# controlled_boost_converter_ch0.net
KiCad netlist of a schematic drawn in Altium Designer
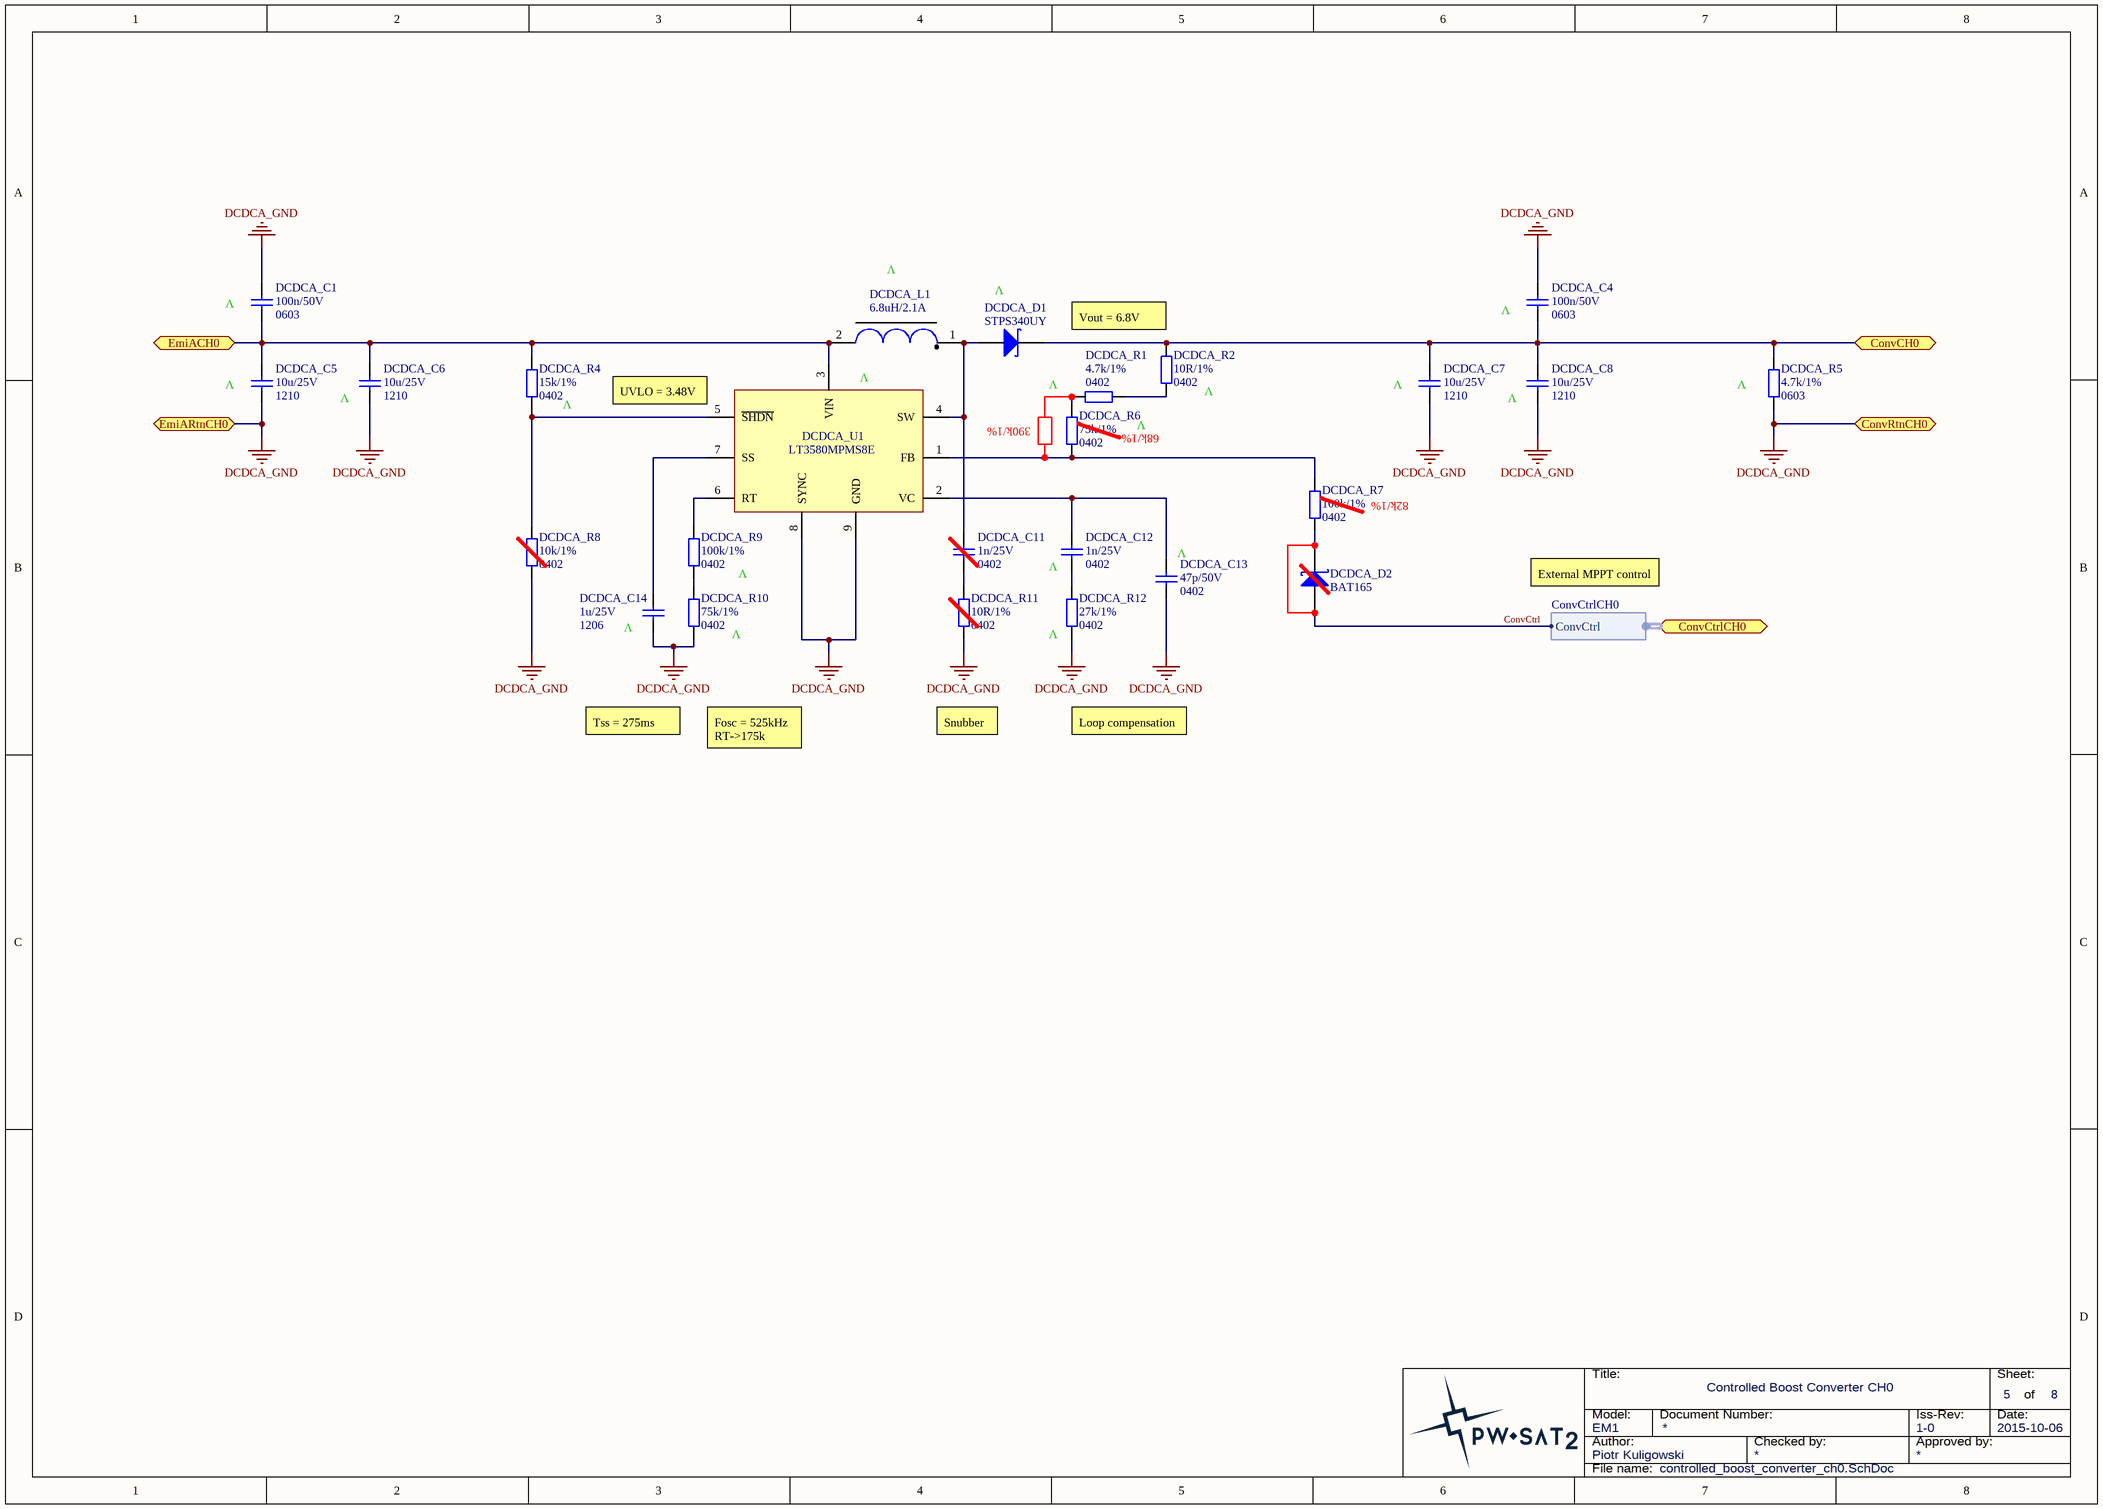
[diagram p0: controlled_boost_converter_ch0.SchDoc]

(export (version "E")
  (design (tool "Eeschema 10.0.6"))
  (components
    (comp (ref "DCDCA_C1")
      (value "100n/50V")
      (footprint "SMD_Capacitor_0603")
      (description "Ceramic Cap Kemet COTS 100n/50V X7R 0603")
      (fields
        (field (name "MANUFACTURER") "Kemet")
        (field (name "MANUFACTURERPARTNUMBER") "C0603T104K5RALTU")
        (field (name "PACKAGE") "0603")
      )
      (libsource (lib "capacitors") (part "Cer_C0603T104K5RALTU"))
    )
    (comp (ref "DCDCA_C4")
      (value "100n/50V")
      (footprint "SMD_Capacitor_0603")
      (description "Ceramic Cap Kemet COTS 100n/50V X7R 0603")
      (fields
        (field (name "MANUFACTURER") "Kemet")
        (field (name "MANUFACTURERPARTNUMBER") "C0603T104K5RALTU")
        (field (name "PACKAGE") "0603")
      )
      (libsource (lib "capacitors") (part "Cer_C0603T104K5RALTU"))
    )
    (comp (ref "DCDCA_C5")
      (value "10u/25V")
      (footprint "SMD_Capacitor_1210")
      (description "Ceramic Cap Murata Automotive 10u/25V X7R 1210")
      (fields
        (field (name "MANUFACTURER") "Murata")
        (field (name "MANUFACTURERPARTNUMBER") "GCJ32ER71E106KA12L")
        (field (name "PACKAGE") "1210")
      )
      (libsource (lib "capacitors") (part "Cer_GCJ32ER71E106KA12L"))
    )
    (comp (ref "DCDCA_C6")
      (value "10u/25V")
      (footprint "SMD_Capacitor_1210")
      (description "Ceramic Cap Murata Automotive 10u/25V X7R 1210")
      (fields
        (field (name "MANUFACTURER") "Murata")
        (field (name "MANUFACTURERPARTNUMBER") "GCJ32ER71E106KA12L")
        (field (name "PACKAGE") "1210")
      )
      (libsource (lib "capacitors") (part "Cer_GCJ32ER71E106KA12L"))
    )
    (comp (ref "DCDCA_C7")
      (value "10u/25V")
      (footprint "SMD_Capacitor_1210")
      (description "Ceramic Cap Murata Automotive 10u/25V X7R 1210")
      (fields
        (field (name "MANUFACTURER") "Murata")
        (field (name "MANUFACTURERPARTNUMBER") "GCJ32ER71E106KA12L")
        (field (name "PACKAGE") "1210")
      )
      (libsource (lib "capacitors") (part "Cer_GCJ32ER71E106KA12L"))
    )
    (comp (ref "DCDCA_C8")
      (value "10u/25V")
      (footprint "SMD_Capacitor_1210")
      (description "Ceramic Cap Murata Automotive 10u/25V X7R 1210")
      (fields
        (field (name "MANUFACTURER") "Murata")
        (field (name "MANUFACTURERPARTNUMBER") "GCJ32ER71E106KA12L")
        (field (name "PACKAGE") "1210")
      )
      (libsource (lib "capacitors") (part "Cer_GCJ32ER71E106KA12L"))
    )
    (comp (ref "DCDCA_C11")
      (value "1n/25V")
      (footprint "SMD_Capacitor_0402")
      (description "Ceramic Cap Kemet COTS 1n/25V C0G 0402.")
      (fields
        (field (name "MANUFACTURER") "Kemet")
        (field (name "MANUFACTURERPARTNUMBER") "C0402T102K3GAL")
        (field (name "PACKAGE") "0402")
      )
      (libsource (lib "capacitors") (part "Cer_C0402T102K3GAL"))
    )
    (comp (ref "DCDCA_C12")
      (value "1n/25V")
      (footprint "SMD_Capacitor_0402")
      (description "Ceramic Cap Kemet COTS 1n/25V C0G 0402.")
      (fields
        (field (name "MANUFACTURER") "Kemet")
        (field (name "MANUFACTURERPARTNUMBER") "C0402T102K3GAL")
        (field (name "PACKAGE") "0402")
      )
      (libsource (lib "capacitors") (part "Cer_C0402T102K3GAL"))
    )
    (comp (ref "DCDCA_C13")
      (value "47p/50V")
      (footprint "SMD_Capacitor_0402")
      (description "Ceramic Cap Murata Automotive 47p/50V C0G 0402")
      (fields
        (field (name "MANUFACTURER") "Murata")
        (field (name "MANUFACTURERPARTNUMBER") "GCM1555C1H470JA16D")
        (field (name "PACKAGE") "0402")
      )
      (libsource (lib "capacitors") (part "Cer_GCM1555C1H470JA16D"))
    )
    (comp (ref "DCDCA_C14")
      (value "1u/25V")
      (footprint "SMD_Capacitor_1206")
      (description "Ceramic Cap Kemet COTS 1u/25V X7R 1206")
      (fields
        (field (name "MANUFACTURERPARTNUMBER") "C1206T105K3RALTU")
        (field (name "MANUFACTURER") "Kemet")
        (field (name "PACKAGE") "1206")
      )
      (libsource (lib "capacitors") (part "Cer_C1206T105K3RALTU"))
    )
    (comp (ref "DCDCA_D1")
      (value "STPS340UY")
      (footprint "DO-214AA")
      (description "3A/40V Power Schottky Rectifier.")
      (fields (field (name "MANUFACTURER") "STMicroelectronics"))
      (libsource (lib "diodes") (part "STPS340x"))
    )
    (comp (ref "DCDCA_D2")
      (value "BAT165")
      (footprint "SOD323")
      (description "Madium Power AF Schottky 750mA 40V Diode")
      (fields (field (name "MANUFACTURER") "Infineon"))
      (libsource (lib "diodes") (part "BAT165"))
    )
    (comp (ref "DCDCA_L1")
      (value "6.8uH/2.1A")
      (footprint "Coilcraft_MSS6132")
      (description "Coilcraft MSS6132 Inductor, L=6.8uH, Irise20deg=2.1A, ESR=52mR, SRF=47MHz.")
      (fields
        (field (name "MANUFACTURER") "Coilcraft")
        (field (name "MANUFACTURERPARTNUMBER") "MSS6132-682MLx")
      )
      (libsource (lib "inductors") (part "MSS6132-682MLx"))
    )
    (comp (ref "DCDCA_R1")
      (value "4.7k/1%")
      (footprint "SMD_Resistor_0402")
      (description "4.7k/1% Vishay CRCW 0402 Resistor. 63mW, 100ppm, 50V.")
      (fields
        (field (name "MANUFACTURERPARTNUMBER") "CRCW04024K70FKxxxx")
        (field (name "MANUFACTURER") "Vishay")
        (field (name "PACKAGE") "0402")
      )
      (libsource (lib "resistors") (part "CRCW04024K70FKxxxx"))
    )
    (comp (ref "DCDCA_R2")
      (value "10R/1%")
      (footprint "SMD_Resistor_0402")
      (description "10R/1% Vishay CRCW 0402 Resistor. 63mW, 100ppm, 50V.")
      (fields
        (field (name "MANUFACTURER") "Vishay")
        (field (name "MANUFACTURERPARTNUMBER") "CRCW040210R0FKxxxx")
        (field (name "PACKAGE") "0402")
      )
      (libsource (lib "resistors") (part "CRCW040210R0FKxxxx"))
    )
    (comp (ref "DCDCA_R4")
      (value "15k/1%")
      (footprint "SMD_Resistor_0402")
      (description "15k/1% Vishay CRCW 0402 Resistor. 63mW, 100ppm, 50V.")
      (fields
        (field (name "MANUFACTURER") "Vishay")
        (field (name "MANUFACTURERPARTNUMBER") "CRCW040215K0FKxxxx")
        (field (name "PACKAGE") "0402")
      )
      (libsource (lib "resistors") (part "CRCW040215K0FKxxxx"))
    )
    (comp (ref "DCDCA_R5")
      (value "4.7k/1%")
      (footprint "SMD_Resistor_0603")
      (description "4.7k/1% Vishay CRCW 0603 Resistor. 100mW, 100ppm, 75V.")
      (fields
        (field (name "MANUFACTURER") "Vishay")
        (field (name "MANUFACTUERPARTNUMBER") "CRCW06034K70FKxxxx")
        (field (name "PACKAGE") "0603")
      )
      (libsource (lib "resistors") (part "CRCW06034K70FKxxxx"))
    )
    (comp (ref "DCDCA_R6")
      (value "75k/1%")
      (footprint "SMD_Resistor_0402")
      (description "75k/1% Vishay CRCW 0402 Resistor. 63mW, 100ppm, 50V.")
      (fields
        (field (name "MANUFACTURERPARTNUMBER") "CRCW040275K0FK")
        (field (name "MANUFACTURER") "Vishay")
        (field (name "PACKAGE") "0402")
      )
      (libsource (lib "resistors") (part "CRCW040275K0FKxxxx"))
    )
    (comp (ref "DCDCA_R7")
      (value "100k/1%")
      (footprint "SMD_Resistor_0402")
      (description "100k/1% Vishay CRCW 0402 Resistor. 63mW, 100ppm, 50V.")
      (fields
        (field (name "MANUFACTURER") "Vishay")
        (field (name "MANUFACTURERPARTNUMBER") "CRCW0402100KFKxxxx")
        (field (name "PACKAGE") "0402")
      )
      (libsource (lib "resistors") (part "CRCW0402100KFKxxxx"))
    )
    (comp (ref "DCDCA_R8")
      (value "10k/1%")
      (footprint "SMD_Resistor_0402")
      (description "10k/1% Vishay CRCW 0402 Resistor. 63mW, 100ppm, 50V.")
      (fields
        (field (name "MANUFACTURER") "Vishay")
        (field (name "MANUFACTURERPARTNUMBER") "CRCW040210K0FKxxxx")
        (field (name "PACKAGE") "0402")
      )
      (libsource (lib "resistors") (part "CRCW040210K0FKxxxx"))
    )
    (comp (ref "DCDCA_R9")
      (value "100k/1%")
      (footprint "SMD_Resistor_0402")
      (description "100k/1% Vishay CRCW 0402 Resistor. 63mW, 100ppm, 50V.")
      (fields
        (field (name "MANUFACTURER") "Vishay")
        (field (name "MANUFACTURERPARTNUMBER") "CRCW0402100KFKxxxx")
        (field (name "PACKAGE") "0402")
      )
      (libsource (lib "resistors") (part "CRCW0402100KFKxxxx"))
    )
    (comp (ref "DCDCA_R10")
      (value "75k/1%")
      (footprint "SMD_Resistor_0402")
      (description "75k/1% Vishay CRCW 0402 Resistor. 63mW, 100ppm, 50V.")
      (fields
        (field (name "MANUFACTURERPARTNUMBER") "CRCW040275K0FK")
        (field (name "MANUFACTURER") "Vishay")
        (field (name "PACKAGE") "0402")
      )
      (libsource (lib "resistors") (part "CRCW040275K0FKxxxx"))
    )
    (comp (ref "DCDCA_R11")
      (value "10R/1%")
      (footprint "SMD_Resistor_0402")
      (description "10R/1% Vishay CRCW 0402 Resistor. 63mW, 100ppm, 50V.")
      (fields
        (field (name "MANUFACTURER") "Vishay")
        (field (name "MANUFACTURERPARTNUMBER") "CRCW040210R0FKxxxx")
        (field (name "PACKAGE") "0402")
      )
      (libsource (lib "resistors") (part "CRCW040210R0FKxxxx"))
    )
    (comp (ref "DCDCA_R12")
      (value "27k/1%")
      (footprint "SMD_Resistor_0402")
      (description "27k/1% Vishay CRCW 0402 Resistor. 63mW, 100ppm, 50V.")
      (fields
        (field (name "MANUFACTURER") "Vishay")
        (field (name "MANUFACTURERPARTNUMBER") "CRCW040227K0FKxxxx")
        (field (name "PACKAGE") "0402")
      )
      (libsource (lib "resistors") (part "CRCW040227K0FKxxxx"))
    )
    (comp (ref "DCDCA_U1")
      (value "~")
      (footprint "LT-MS8E-8-1880X1680TP_N")
      (description "Boost Conv 2A, Soft-Start, Synchro")
      (fields
        (field (name "MANUFACTURER") "Linear Technology")
        (field (name "MANUFACTURERPARTNUMBER") "LT3580MPMS8E")
      )
      (libsource (lib "microcircuits") (part "LT3580MPMS8E"))
    )
  )
  (nets
    (net (code "2") (name "/ConvCH0") (class "Default")
      (node (ref "DCDCA_C4") (pin "1") (pinfunction "1_1") (pintype "passive"))
      (node (ref "DCDCA_C7") (pin "1") (pinfunction "1_1") (pintype "passive"))
      (node (ref "DCDCA_C8") (pin "1") (pinfunction "1_1") (pintype "passive"))
      (node (ref "DCDCA_D1") (pin "K") (pinfunction "K_K") (pintype "passive"))
      (node (ref "DCDCA_R2") (pin "1") (pinfunction "1_1") (pintype "passive"))
      (node (ref "DCDCA_R5") (pin "1") (pinfunction "1_1") (pintype "passive"))
    )
    (net (code "3") (name "/ConvCtrl") (class "Default")
      (node (ref "DCDCA_D2") (pin "A") (pinfunction "A_A") (pintype "passive"))
    )
    (net (code "4") (name "/EmiACH0") (class "Default")
      (node (ref "DCDCA_C1") (pin "1") (pinfunction "1_1") (pintype "passive"))
      (node (ref "DCDCA_C5") (pin "1") (pinfunction "1_1") (pintype "passive"))
      (node (ref "DCDCA_C6") (pin "1") (pinfunction "1_1") (pintype "passive"))
      (node (ref "DCDCA_L1") (pin "2") (pinfunction "2_2") (pintype "passive"))
      (node (ref "DCDCA_R4") (pin "1") (pinfunction "1_1") (pintype "passive"))
      (node (ref "DCDCA_U1") (pin "3") (pinfunction "VIN_3") (pintype "power_in"))
    )
    (net (code "6") (name "DCDCA_GND") (class "Default")
      (node (ref "DCDCA_C1") (pin "2") (pinfunction "2_2") (pintype "passive"))
      (node (ref "DCDCA_C13") (pin "2") (pinfunction "2_2") (pintype "passive"))
      (node (ref "DCDCA_C14") (pin "2") (pinfunction "2_2") (pintype "passive"))
      (node (ref "DCDCA_C4") (pin "2") (pinfunction "2_2") (pintype "passive"))
      (node (ref "DCDCA_C5") (pin "2") (pinfunction "2_2") (pintype "passive"))
      (node (ref "DCDCA_C6") (pin "2") (pinfunction "2_2") (pintype "passive"))
      (node (ref "DCDCA_C7") (pin "2") (pinfunction "2_2") (pintype "passive"))
      (node (ref "DCDCA_C8") (pin "2") (pinfunction "2_2") (pintype "passive"))
      (node (ref "DCDCA_R10") (pin "2") (pinfunction "2_2") (pintype "passive"))
      (node (ref "DCDCA_R11") (pin "2") (pinfunction "2_2") (pintype "passive"))
      (node (ref "DCDCA_R12") (pin "2") (pinfunction "2_2") (pintype "passive"))
      (node (ref "DCDCA_R5") (pin "2") (pinfunction "2_2") (pintype "passive"))
      (node (ref "DCDCA_R8") (pin "2") (pinfunction "2_2") (pintype "passive"))
      (node (ref "DCDCA_U1") (pin "8") (pinfunction "SYNC_8") (pintype "passive"))
      (node (ref "DCDCA_U1") (pin "9") (pinfunction "GND_9") (pintype "passive"))
    )
    (net (code "7") (name "Net-(DCDCA_C11-Pad2)") (class "Default")
      (node (ref "DCDCA_C11") (pin "2") (pinfunction "2_2") (pintype "passive"))
      (node (ref "DCDCA_R11") (pin "1") (pinfunction "1_1") (pintype "passive"))
    )
    (net (code "8") (name "Net-(DCDCA_C12-Pad2)") (class "Default")
      (node (ref "DCDCA_C12") (pin "2") (pinfunction "2_2") (pintype "passive"))
      (node (ref "DCDCA_R12") (pin "1") (pinfunction "1_1") (pintype "passive"))
    )
    (net (code "9") (name "Net-(DCDCA_D2-PadK)") (class "Default")
      (node (ref "DCDCA_D2") (pin "K") (pinfunction "K_K") (pintype "passive"))
      (node (ref "DCDCA_R7") (pin "2") (pinfunction "2_2") (pintype "passive"))
    )
    (net (code "10") (name "Net-(DCDCA_R1-Pad1)") (class "Default")
      (node (ref "DCDCA_R1") (pin "1") (pinfunction "1_1") (pintype "passive"))
      (node (ref "DCDCA_R6") (pin "1") (pinfunction "1_1") (pintype "passive"))
    )
    (net (code "11") (name "Net-(DCDCA_R1-Pad2)") (class "Default")
      (node (ref "DCDCA_R1") (pin "2") (pinfunction "2_2") (pintype "passive"))
      (node (ref "DCDCA_R2") (pin "2") (pinfunction "2_2") (pintype "passive"))
    )
    (net (code "12") (name "Net-(DCDCA_R10-Pad1)") (class "Default")
      (node (ref "DCDCA_R10") (pin "1") (pinfunction "1_1") (pintype "passive"))
      (node (ref "DCDCA_R9") (pin "2") (pinfunction "2_2") (pintype "passive"))
    )
    (net (code "13") (name "Net-(DCDCA_U1-FB)") (class "Default")
      (node (ref "DCDCA_R6") (pin "2") (pinfunction "2_2") (pintype "passive"))
      (node (ref "DCDCA_R7") (pin "1") (pinfunction "1_1") (pintype "passive"))
      (node (ref "DCDCA_U1") (pin "1") (pinfunction "FB_1") (pintype "passive"))
    )
    (net (code "14") (name "Net-(DCDCA_U1-RT)") (class "Default")
      (node (ref "DCDCA_R9") (pin "1") (pinfunction "1_1") (pintype "passive"))
      (node (ref "DCDCA_U1") (pin "6") (pinfunction "RT_6") (pintype "passive"))
    )
    (net (code "15") (name "Net-(DCDCA_U1-SS)") (class "Default")
      (node (ref "DCDCA_C14") (pin "1") (pinfunction "1_1") (pintype "passive"))
      (node (ref "DCDCA_U1") (pin "7") (pinfunction "SS_7") (pintype "passive"))
    )
    (net (code "16") (name "Net-(DCDCA_U1-SW)") (class "Default")
      (node (ref "DCDCA_C11") (pin "1") (pinfunction "1_1") (pintype "passive"))
      (node (ref "DCDCA_D1") (pin "A") (pinfunction "A_A") (pintype "passive"))
      (node (ref "DCDCA_L1") (pin "1") (pinfunction "1_1") (pintype "passive"))
      (node (ref "DCDCA_U1") (pin "4") (pinfunction "SW_4") (pintype "passive"))
    )
    (net (code "17") (name "Net-(DCDCA_U1-VC)") (class "Default")
      (node (ref "DCDCA_C12") (pin "1") (pinfunction "1_1") (pintype "passive"))
      (node (ref "DCDCA_C13") (pin "1") (pinfunction "1_1") (pintype "passive"))
      (node (ref "DCDCA_U1") (pin "2") (pinfunction "VC_2") (pintype "passive"))
    )
    (net (code "18") (name "Net-(DCDCA_U1-~{SHDN})") (class "Default")
      (node (ref "DCDCA_R4") (pin "2") (pinfunction "2_2") (pintype "passive"))
      (node (ref "DCDCA_R8") (pin "1") (pinfunction "1_1") (pintype "passive"))
      (node (ref "DCDCA_U1") (pin "5") (pinfunction "~{SHDN}_5") (pintype "passive"))
    )
  )
)
